# 467444_130_3_4-R0.net
KiCad netlist of a schematic drawn in Altium Designer
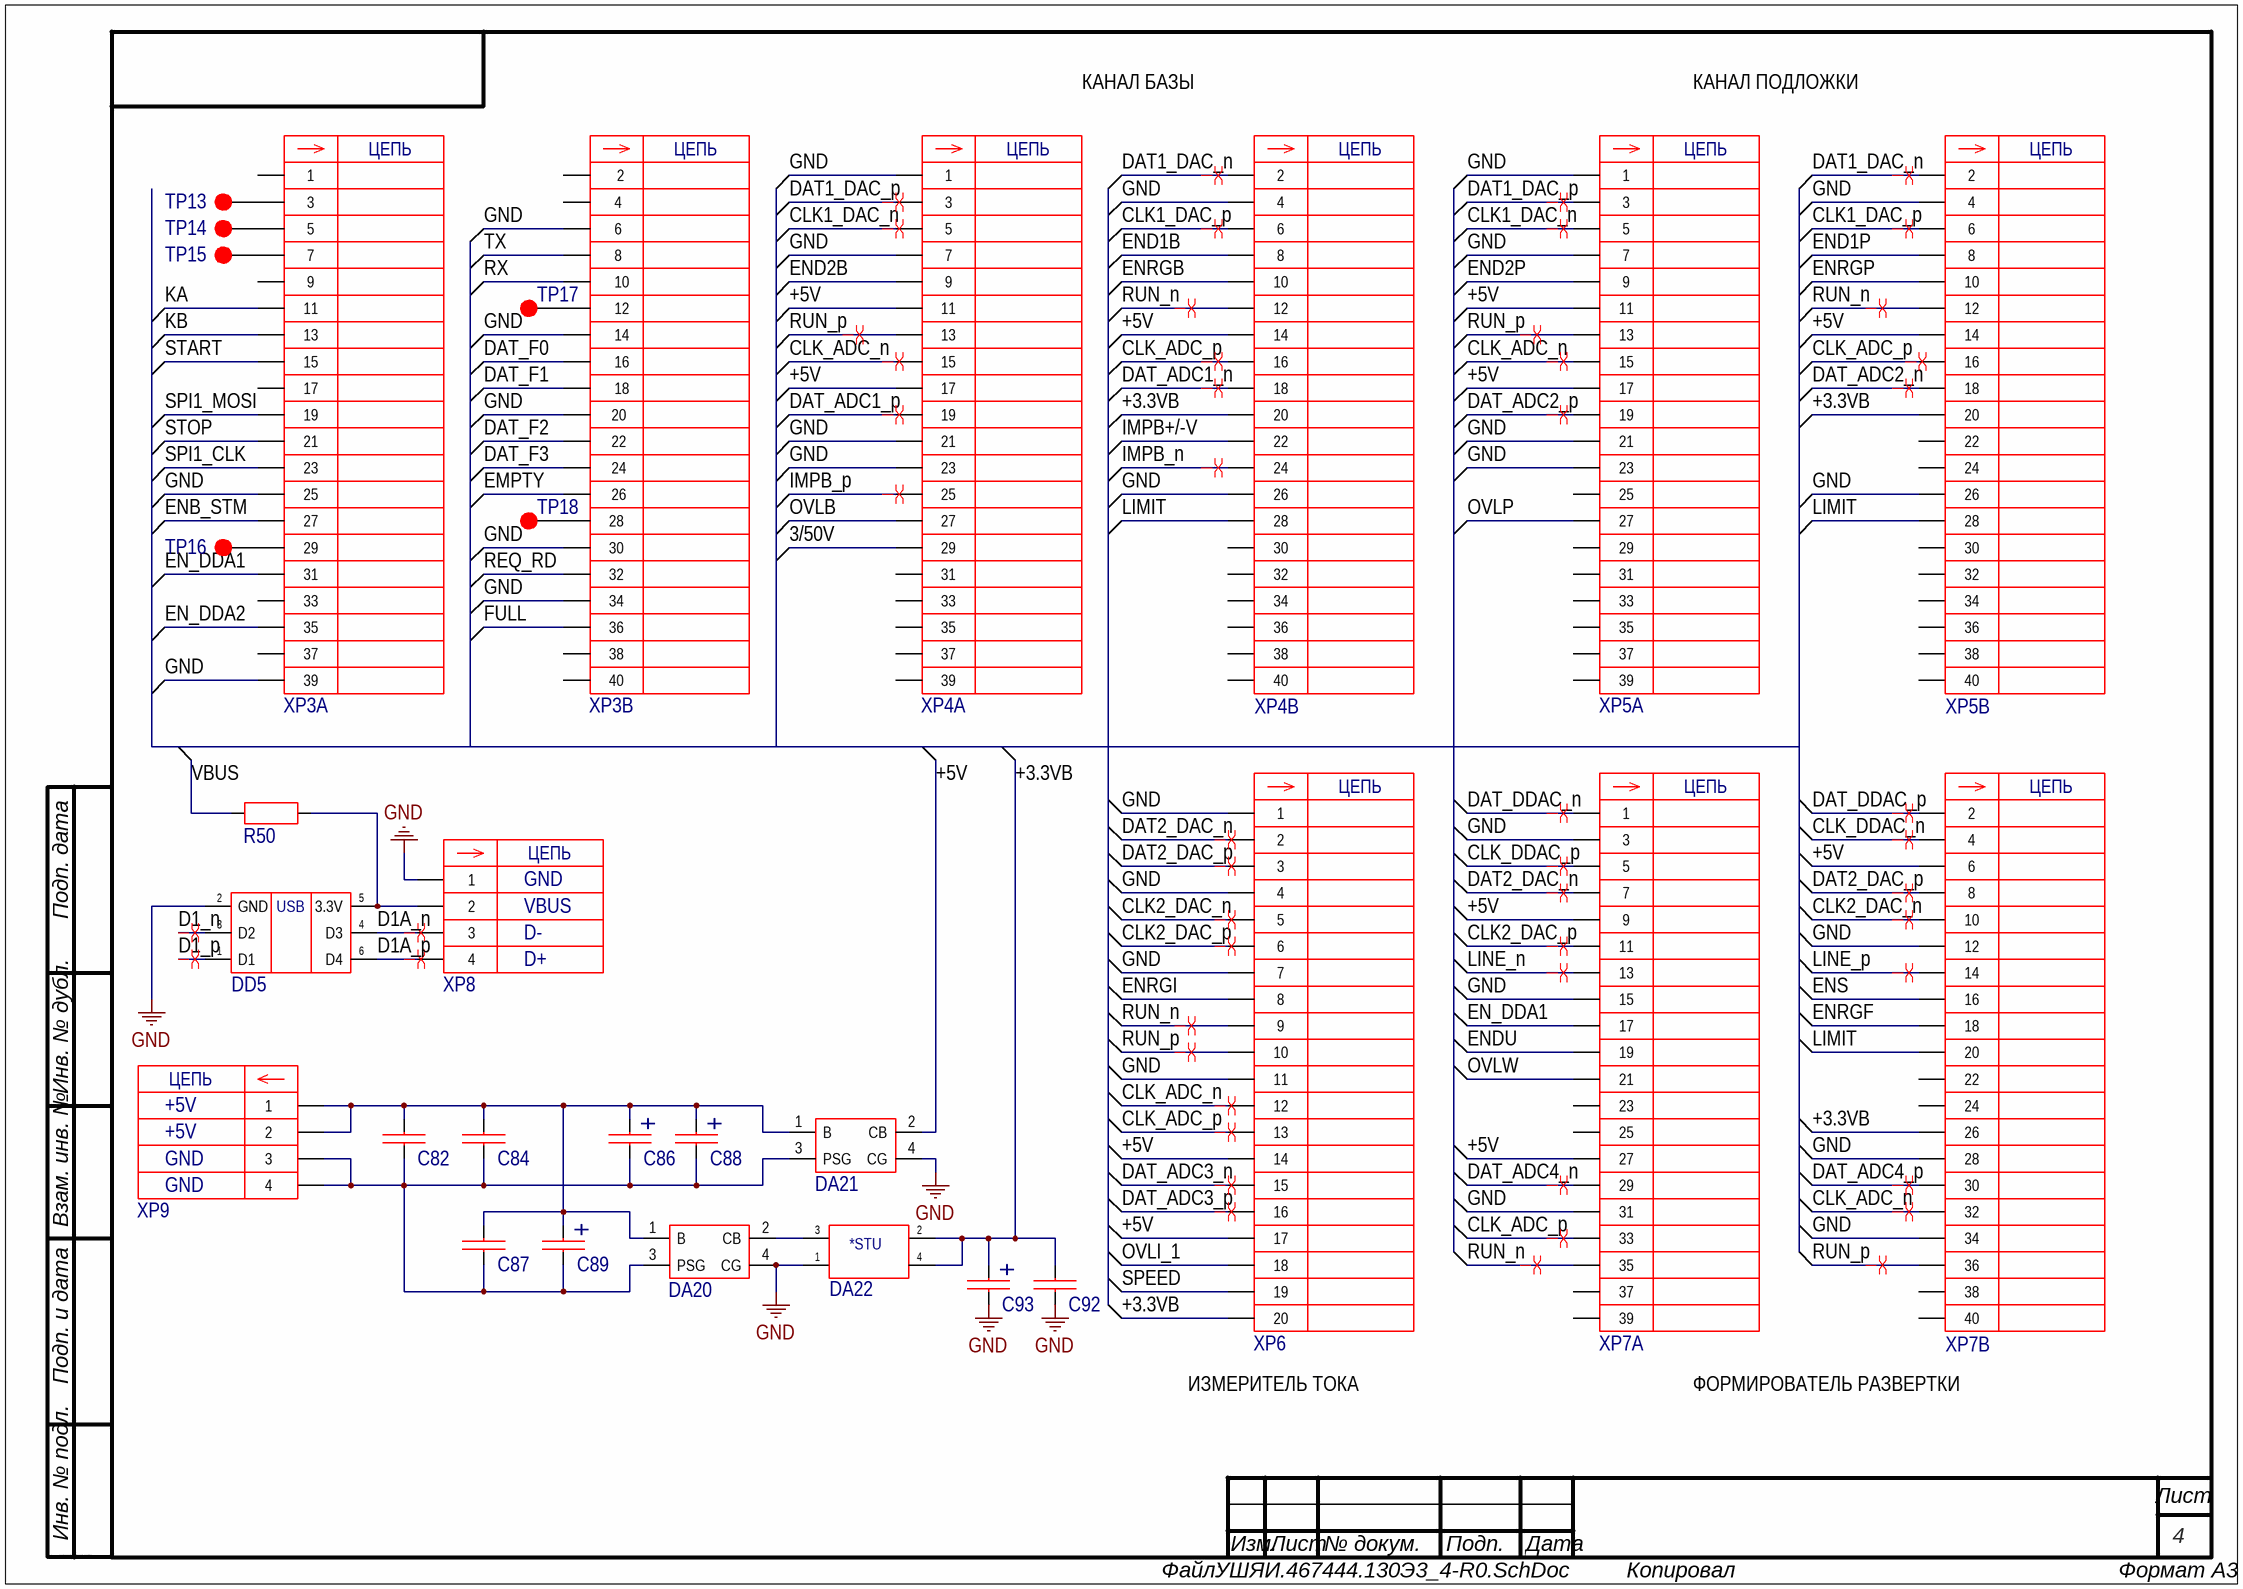
[diagram p0: УШЯИ.467444.130Э3_4-R0.SchDoc]

(export (version "E")
  (design (tool "Eeschema 10.0.6"))
  (components
    (comp (ref "C82")
      (value "0,1 µF")
      (footprint "C_0805 [2012 Metric]")
      (description "Неполярный конденсатор")
      (fields (field (name "MANUFACTURER") "Murata") (field (name "VOLTAGE") "50V"))
      (libsource (lib "lib") (part "C_const"))
    )
    (comp (ref "C84")
      (value "0,1 µF")
      (footprint "C_0805 [2012 Metric]")
      (description "Неполярный конденсатор")
      (fields (field (name "MANUFACTURER") "Murata") (field (name "VOLTAGE") "50V"))
      (libsource (lib "lib") (part "C_const"))
    )
    (comp (ref "C86")
      (value "1000 µF")
      (footprint "С_EXR_10x21")
      (description "Полярный конденсатор")
      (fields (field (name "MANUFACTURER") "Hitano") (field (name "VOLTAGE") "16V"))
      (libsource (lib "lib") (part "C_electrolytic"))
    )
    (comp (ref "C87")
      (value "0,1 µF")
      (footprint "C_0805 [2012 Metric]")
      (description "Неполярный конденсатор")
      (fields (field (name "MANUFACTURER") "Murata") (field (name "VOLTAGE") "50V"))
      (libsource (lib "lib") (part "C_const"))
    )
    (comp (ref "C88")
      (value "10 µF")
      (footprint "C+_1210 [3528-21 Metric]")
      (description "Полярный конденсатор")
      (fields (field (name "MANUFACTURER") "KYOCERA AVX") (field (name "VOLTAGE") "20V\r\n10V"))
      (libsource (lib "lib") (part "C_electrolytic"))
    )
    (comp (ref "C89")
      (value "10 µF")
      (footprint "C+_1210 [3528-21 Metric]")
      (description "Полярный конденсатор")
      (fields (field (name "MANUFACTURER") "KYOCERA AVX") (field (name "VOLTAGE") "20V\r\n10V"))
      (libsource (lib "lib") (part "C_electrolytic"))
    )
    (comp (ref "C92")
      (value "0,1 µF")
      (footprint "C_0805 [2012 Metric]")
      (description "Неполярный конденсатор")
      (fields (field (name "MANUFACTURER") "Murata") (field (name "VOLTAGE") "50V"))
      (libsource (lib "lib") (part "C_const"))
    )
    (comp (ref "C93")
      (value "10 µF")
      (footprint "C+_1210 [3528-21 Metric]")
      (description "Полярный конденсатор")
      (fields (field (name "MANUFACTURER") "KYOCERA AVX") (field (name "VOLTAGE") "20V\r\n10V"))
      (libsource (lib "lib") (part "C_electrolytic"))
    )
    (comp (ref "DA20")
      (value "BNX028-01")
      (footprint "F_BNX028-01")
      (description "16В, 35дБ")
      (fields (field (name "MANUFACTURER") "Murata Electronics"))
      (libsource (lib "lib") (part "F_BNX022-01"))
    )
    (comp (ref "DA21")
      (value "BNX028-01")
      (footprint "F_BNX028-01")
      (description "16В, 35дБ")
      (fields (field (name "MANUFACTURER") "Murata Electronics"))
      (libsource (lib "lib") (part "F_BNX022-01"))
    )
    (comp (ref "DA22")
      (value "LD1117AS33TR")
      (footprint "SOT-223")
      (description "IC, Fixed LDO Voltage Regulator, 5.3V to 10V, 1.15V Dropout, 3.3Vout, 1Aout")
      (fields (field (name "MANUFACTURER") "STMicroelectronics"))
      (libsource (lib "lib") (part "VolReg_LD1117AS33TR"))
    )
    (comp (ref "DD5")
      (value "USBUF01W6")
      (footprint "SOT-323-6")
      (description "EMI Filter, 2-Channel, USB Upstream Terminator, ESD Protection")
      (fields (field (name "MANUFACTURER") "STMicroelectronics"))
      (libsource (lib "lib") (part "USBUF01W6"))
    )
    (comp (ref "R50")
      (value "30R")
      (footprint "R_0805 [2012 Metric]")
      (fields (field (name "TOLERANCE") "±5%"))
      (libsource (lib "lib") (part "R_Const"))
    )
    (comp (ref "TP13") (value "~") (footprint "DSP_1.3") (libsource (lib "lib") (part "TP")))
    (comp (ref "TP14") (value "~") (footprint "DSP_1.3") (libsource (lib "lib") (part "TP")))
    (comp (ref "TP15") (value "~") (footprint "DSP_1.3") (libsource (lib "lib") (part "TP")))
    (comp (ref "TP16") (value "~") (footprint "DSP_1.3") (libsource (lib "lib") (part "TP")))
    (comp (ref "TP17") (value "~") (footprint "DSP_1.3") (libsource (lib "lib") (part "TP")))
    (comp (ref "TP18") (value "~") (footprint "DSP_1.3") (libsource (lib "lib") (part "TP")))
    (comp (ref "XP3")
      (value "BH-40")
      (footprint "BH-40")
      (description "Male, 40 pins, 2 rows, Vertical, DS1013-40S, 2.54 mm")
      (fields (field (name "MANUFACTURER") "Connfly electronic"))
      (libsource (lib "lib") (part "M_40"))
    )
    (comp (ref "XP4")
      (value "BH2-40")
      (footprint "BH2-40")
      (description "Male, 40 pins, 2 rows, Vertical, DS1014-40, 2 mm")
      (fields (field (name "MANUFACTURER") "Connfly electronic"))
      (libsource (lib "lib") (part "M_40"))
    )
    (comp (ref "XP5")
      (value "BH2-40")
      (footprint "BH2-40")
      (description "Male, 40 pins, 2 rows, Vertical, DS1014-40, 2 mm")
      (fields (field (name "MANUFACTURER") "Connfly electronic"))
      (libsource (lib "lib") (part "M_40"))
    )
    (comp (ref "XP6")
      (value "BH2-20R")
      (footprint "BH2-20R")
      (description "Male, 20 pins, 2 rows, Right Angle, DS1014-20RF1B-B, 2 mm")
      (fields (field (name "MANUFACTURER") "Connfly electronic"))
      (libsource (lib "lib") (part "M_20"))
    )
    (comp (ref "XP7")
      (value "BH2-40")
      (footprint "BH2-40")
      (description "Male, 40 pins, 2 rows, Vertical, DS1014-40, 2 mm")
      (fields (field (name "MANUFACTURER") "Connfly electronic"))
      (libsource (lib "lib") (part "M_40"))
    )
    (comp (ref "XP8")
      (value "AMPMODU II 280371-2")
      (footprint "AMP II-280371-2")
      (description "Male, 4 pin, 1 row, Vertical, Board-to-Board, 2.54 mm")
      (fields (field (name "MANUFACTURER") "TE Connectivity"))
      (libsource (lib "") (part "M_4_1"))
    )
    (comp (ref "XP9")
      (value "AMPMODU II 280371-2")
      (footprint "AMP II-280371-2")
      (description "Male, 4 pin, 1 row, Vertical, Board-to-Board, 2.54 mm")
      (fields (field (name "MANUFACTURER") "TE Connectivity"))
      (libsource (lib "lib") (part "M_4"))
    )
  )
  (nets
    (net (code "1") (name "/+3.3VB") (class "Default")
      (node (ref "C92") (pin "2") (pinfunction "2_2") (pintype "passive"))
      (node (ref "C93") (pin "+") (pinfunction "+_+") (pintype "passive"))
      (node (ref "DA22") (pin "2") (pinfunction "VOUT_2") (pintype "passive"))
      (node (ref "DA22") (pin "4") (pinfunction "VOUT_4") (pintype "passive"))
      (node (ref "XP4") (pin "20") (pinfunction "20_20") (pintype "passive"))
      (node (ref "XP5") (pin "20") (pinfunction "20_20") (pintype "passive"))
      (node (ref "XP6") (pin "20") (pinfunction "20_20") (pintype "passive"))
      (node (ref "XP7") (pin "26") (pinfunction "26_26") (pintype "passive"))
    )
    (net (code "2") (name "/+5V") (class "Default")
      (node (ref "DA21") (pin "2") (pinfunction "CB_2") (pintype "passive"))
      (node (ref "XP4") (pin "11") (pinfunction "11_11") (pintype "passive"))
      (node (ref "XP4") (pin "14") (pinfunction "14_14") (pintype "passive"))
      (node (ref "XP4") (pin "17") (pinfunction "17_17") (pintype "passive"))
      (node (ref "XP5") (pin "11") (pinfunction "11_11") (pintype "passive"))
      (node (ref "XP5") (pin "14") (pinfunction "14_14") (pintype "passive"))
      (node (ref "XP5") (pin "17") (pinfunction "17_17") (pintype "passive"))
      (node (ref "XP6") (pin "14") (pinfunction "14_14") (pintype "passive"))
      (node (ref "XP6") (pin "17") (pinfunction "17_17") (pintype "passive"))
      (node (ref "XP7") (pin "27") (pinfunction "27_27") (pintype "passive"))
      (node (ref "XP7") (pin "6") (pinfunction "6_6") (pintype "passive"))
      (node (ref "XP7") (pin "9") (pinfunction "9_9") (pintype "passive"))
    )
    (net (code "3") (name "/3{slash}50V") (class "Default")
      (node (ref "XP4") (pin "29") (pinfunction "29_29") (pintype "passive"))
    )
    (net (code "4") (name "/CLK1_DAC_n") (class "Default")
      (node (ref "XP4") (pin "5") (pinfunction "5_5") (pintype "passive"))
      (node (ref "XP5") (pin "5") (pinfunction "5_5") (pintype "passive"))
    )
    (net (code "5") (name "/CLK1_DAC_p") (class "Default")
      (node (ref "XP4") (pin "6") (pinfunction "6_6") (pintype "passive"))
      (node (ref "XP5") (pin "6") (pinfunction "6_6") (pintype "passive"))
    )
    (net (code "6") (name "/CLK2_DAC_n") (class "Default")
      (node (ref "XP6") (pin "5") (pinfunction "5_5") (pintype "passive"))
      (node (ref "XP7") (pin "10") (pinfunction "10_10") (pintype "passive"))
    )
    (net (code "7") (name "/CLK2_DAC_p") (class "Default")
      (node (ref "XP6") (pin "6") (pinfunction "6_6") (pintype "passive"))
      (node (ref "XP7") (pin "11") (pinfunction "11_11") (pintype "passive"))
    )
    (net (code "8") (name "/CLK_ADC_n") (class "Default")
      (node (ref "XP4") (pin "15") (pinfunction "15_15") (pintype "passive"))
      (node (ref "XP5") (pin "15") (pinfunction "15_15") (pintype "passive"))
      (node (ref "XP6") (pin "12") (pinfunction "12_12") (pintype "passive"))
      (node (ref "XP7") (pin "32") (pinfunction "32_32") (pintype "passive"))
    )
    (net (code "9") (name "/CLK_ADC_p") (class "Default")
      (node (ref "XP4") (pin "16") (pinfunction "16_16") (pintype "passive"))
      (node (ref "XP5") (pin "16") (pinfunction "16_16") (pintype "passive"))
      (node (ref "XP6") (pin "13") (pinfunction "13_13") (pintype "passive"))
      (node (ref "XP7") (pin "33") (pinfunction "33_33") (pintype "passive"))
    )
    (net (code "10") (name "/CLK_DDAC_n") (class "Default")
      (node (ref "XP7") (pin "4") (pinfunction "4_4") (pintype "passive"))
    )
    (net (code "11") (name "/CLK_DDAC_p") (class "Default")
      (node (ref "XP7") (pin "5") (pinfunction "5_5") (pintype "passive"))
    )
    (net (code "12") (name "/D1A_n") (class "Default")
      (node (ref "DD5") (pin "4") (pinfunction "D3_4") (pintype "passive"))
      (node (ref "XP8") (pin "3") (pinfunction "3_3") (pintype "passive"))
    )
    (net (code "13") (name "/D1A_p") (class "Default")
      (node (ref "DD5") (pin "6") (pinfunction "D4_6") (pintype "passive"))
      (node (ref "XP8") (pin "4") (pinfunction "4_4") (pintype "passive"))
    )
    (net (code "14") (name "/D1_n") (class "Default")
      (node (ref "DD5") (pin "3") (pinfunction "D2_3") (pintype "passive"))
    )
    (net (code "15") (name "/D1_p") (class "Default")
      (node (ref "DD5") (pin "1") (pinfunction "D1_1") (pintype "passive"))
    )
    (net (code "16") (name "/DAT1_DAC_n") (class "Default")
      (node (ref "XP4") (pin "2") (pinfunction "2_2") (pintype "passive"))
      (node (ref "XP5") (pin "2") (pinfunction "2_2") (pintype "passive"))
    )
    (net (code "17") (name "/DAT1_DAC_p") (class "Default")
      (node (ref "XP4") (pin "3") (pinfunction "3_3") (pintype "passive"))
      (node (ref "XP5") (pin "3") (pinfunction "3_3") (pintype "passive"))
    )
    (net (code "18") (name "/DAT2_DAC_n") (class "Default")
      (node (ref "XP6") (pin "2") (pinfunction "2_2") (pintype "passive"))
      (node (ref "XP7") (pin "7") (pinfunction "7_7") (pintype "passive"))
    )
    (net (code "19") (name "/DAT2_DAC_p") (class "Default")
      (node (ref "XP6") (pin "3") (pinfunction "3_3") (pintype "passive"))
      (node (ref "XP7") (pin "8") (pinfunction "8_8") (pintype "passive"))
    )
    (net (code "20") (name "/DAT_ADC1_n") (class "Default")
      (node (ref "XP4") (pin "18") (pinfunction "18_18") (pintype "passive"))
    )
    (net (code "21") (name "/DAT_ADC1_p") (class "Default")
      (node (ref "XP4") (pin "19") (pinfunction "19_19") (pintype "passive"))
    )
    (net (code "22") (name "/DAT_ADC2_n") (class "Default")
      (node (ref "XP5") (pin "18") (pinfunction "18_18") (pintype "passive"))
    )
    (net (code "23") (name "/DAT_ADC2_p") (class "Default")
      (node (ref "XP5") (pin "19") (pinfunction "19_19") (pintype "passive"))
    )
    (net (code "24") (name "/DAT_ADC3_n") (class "Default")
      (node (ref "XP6") (pin "15") (pinfunction "15_15") (pintype "passive"))
    )
    (net (code "25") (name "/DAT_ADC3_p") (class "Default")
      (node (ref "XP6") (pin "16") (pinfunction "16_16") (pintype "passive"))
    )
    (net (code "26") (name "/DAT_ADC4_n") (class "Default")
      (node (ref "XP7") (pin "29") (pinfunction "29_29") (pintype "passive"))
    )
    (net (code "27") (name "/DAT_ADC4_p") (class "Default")
      (node (ref "XP7") (pin "30") (pinfunction "30_30") (pintype "passive"))
    )
    (net (code "28") (name "/DAT_DDAC_n") (class "Default")
      (node (ref "XP7") (pin "1") (pinfunction "1_1") (pintype "passive"))
    )
    (net (code "29") (name "/DAT_DDAC_p") (class "Default")
      (node (ref "XP7") (pin "2") (pinfunction "2_2") (pintype "passive"))
    )
    (net (code "30") (name "/DAT_F0") (class "Default")
      (node (ref "XP3") (pin "16") (pinfunction "16_16") (pintype "passive"))
    )
    (net (code "31") (name "/DAT_F1") (class "Default")
      (node (ref "XP3") (pin "18") (pinfunction "18_18") (pintype "passive"))
    )
    (net (code "32") (name "/DAT_F2") (class "Default")
      (node (ref "XP3") (pin "22") (pinfunction "22_22") (pintype "passive"))
    )
    (net (code "33") (name "/DAT_F3") (class "Default")
      (node (ref "XP3") (pin "24") (pinfunction "24_24") (pintype "passive"))
    )
    (net (code "34") (name "/EMPTY") (class "Default")
      (node (ref "XP3") (pin "26") (pinfunction "26_26") (pintype "passive"))
    )
    (net (code "35") (name "/ENB_STM") (class "Default")
      (node (ref "XP3") (pin "27") (pinfunction "27_27") (pintype "passive"))
    )
    (net (code "36") (name "/END1B") (class "Default")
      (node (ref "XP4") (pin "8") (pinfunction "8_8") (pintype "passive"))
    )
    (net (code "37") (name "/END1P") (class "Default")
      (node (ref "XP5") (pin "8") (pinfunction "8_8") (pintype "passive"))
    )
    (net (code "38") (name "/END2B") (class "Default")
      (node (ref "XP4") (pin "9") (pinfunction "9_9") (pintype "passive"))
    )
    (net (code "39") (name "/END2P") (class "Default")
      (node (ref "XP5") (pin "9") (pinfunction "9_9") (pintype "passive"))
    )
    (net (code "40") (name "/ENDU") (class "Default")
      (node (ref "XP7") (pin "19") (pinfunction "19_19") (pintype "passive"))
    )
    (net (code "41") (name "/ENRGB") (class "Default")
      (node (ref "XP4") (pin "10") (pinfunction "10_10") (pintype "passive"))
    )
    (net (code "42") (name "/ENRGF") (class "Default")
      (node (ref "XP7") (pin "18") (pinfunction "18_18") (pintype "passive"))
    )
    (net (code "43") (name "/ENRGI") (class "Default")
      (node (ref "XP6") (pin "8") (pinfunction "8_8") (pintype "passive"))
    )
    (net (code "44") (name "/ENRGP") (class "Default")
      (node (ref "XP5") (pin "10") (pinfunction "10_10") (pintype "passive"))
    )
    (net (code "45") (name "/ENS") (class "Default")
      (node (ref "XP7") (pin "16") (pinfunction "16_16") (pintype "passive"))
    )
    (net (code "46") (name "/EN_DDA1") (class "Default")
      (node (ref "XP3") (pin "31") (pinfunction "31_31") (pintype "passive"))
      (node (ref "XP7") (pin "17") (pinfunction "17_17") (pintype "passive"))
    )
    (net (code "47") (name "/EN_DDA2") (class "Default")
      (node (ref "XP3") (pin "35") (pinfunction "35_35") (pintype "passive"))
    )
    (net (code "48") (name "/FULL") (class "Default")
      (node (ref "XP3") (pin "36") (pinfunction "36_36") (pintype "passive"))
    )
    (net (code "49") (name "/IMPB+{slash}-V") (class "Default")
      (node (ref "XP4") (pin "22") (pinfunction "22_22") (pintype "passive"))
    )
    (net (code "50") (name "/IMPB_n") (class "Default")
      (node (ref "XP4") (pin "24") (pinfunction "24_24") (pintype "passive"))
    )
    (net (code "51") (name "/IMPB_p") (class "Default")
      (node (ref "XP4") (pin "25") (pinfunction "25_25") (pintype "passive"))
    )
    (net (code "52") (name "/KA") (class "Default")
      (node (ref "XP3") (pin "11") (pinfunction "11_11") (pintype "passive"))
    )
    (net (code "53") (name "/KB") (class "Default")
      (node (ref "XP3") (pin "13") (pinfunction "13_13") (pintype "passive"))
    )
    (net (code "54") (name "/LIMIT") (class "Default")
      (node (ref "XP4") (pin "28") (pinfunction "28_28") (pintype "passive"))
      (node (ref "XP5") (pin "28") (pinfunction "28_28") (pintype "passive"))
      (node (ref "XP7") (pin "20") (pinfunction "20_20") (pintype "passive"))
    )
    (net (code "55") (name "/LINE_n") (class "Default")
      (node (ref "XP7") (pin "13") (pinfunction "13_13") (pintype "passive"))
    )
    (net (code "56") (name "/LINE_p") (class "Default")
      (node (ref "XP7") (pin "14") (pinfunction "14_14") (pintype "passive"))
    )
    (net (code "57") (name "/OVLB") (class "Default")
      (node (ref "XP4") (pin "27") (pinfunction "27_27") (pintype "passive"))
    )
    (net (code "58") (name "/OVLI_1") (class "Default")
      (node (ref "XP6") (pin "18") (pinfunction "18_18") (pintype "passive"))
    )
    (net (code "59") (name "/OVLP") (class "Default")
      (node (ref "XP5") (pin "27") (pinfunction "27_27") (pintype "passive"))
    )
    (net (code "60") (name "/OVLW") (class "Default")
      (node (ref "XP7") (pin "21") (pinfunction "21_21") (pintype "passive"))
    )
    (net (code "61") (name "/REQ_RD") (class "Default")
      (node (ref "XP3") (pin "32") (pinfunction "32_32") (pintype "passive"))
    )
    (net (code "62") (name "/RUN_n") (class "Default")
      (node (ref "XP4") (pin "12") (pinfunction "12_12") (pintype "passive"))
      (node (ref "XP5") (pin "12") (pinfunction "12_12") (pintype "passive"))
      (node (ref "XP6") (pin "9") (pinfunction "9_9") (pintype "passive"))
      (node (ref "XP7") (pin "35") (pinfunction "35_35") (pintype "passive"))
    )
    (net (code "63") (name "/RUN_p") (class "Default")
      (node (ref "XP4") (pin "13") (pinfunction "13_13") (pintype "passive"))
      (node (ref "XP5") (pin "13") (pinfunction "13_13") (pintype "passive"))
      (node (ref "XP6") (pin "10") (pinfunction "10_10") (pintype "passive"))
      (node (ref "XP7") (pin "36") (pinfunction "36_36") (pintype "passive"))
    )
    (net (code "64") (name "/RX") (class "Default")
      (node (ref "XP3") (pin "10") (pinfunction "10_10") (pintype "passive"))
    )
    (net (code "65") (name "/SPEED") (class "Default")
      (node (ref "XP6") (pin "19") (pinfunction "19_19") (pintype "passive"))
    )
    (net (code "66") (name "/SPI1_CLK") (class "Default")
      (node (ref "XP3") (pin "23") (pinfunction "23_23") (pintype "passive"))
    )
    (net (code "67") (name "/SPI1_MOSI") (class "Default")
      (node (ref "XP3") (pin "19") (pinfunction "19_19") (pintype "passive"))
    )
    (net (code "68") (name "/START") (class "Default")
      (node (ref "XP3") (pin "15") (pinfunction "15_15") (pintype "passive"))
    )
    (net (code "69") (name "/STOP") (class "Default")
      (node (ref "XP3") (pin "21") (pinfunction "21_21") (pintype "passive"))
    )
    (net (code "70") (name "/TX") (class "Default")
      (node (ref "XP3") (pin "8") (pinfunction "8_8") (pintype "passive"))
    )
    (net (code "71") (name "/VBUS") (class "Default")
      (node (ref "R50") (pin "1") (pinfunction "1_1") (pintype "passive"))
    )
    (net (code "72") (name "GND") (class "Default")
      (node (ref "C92") (pin "1") (pinfunction "1_1") (pintype "passive"))
      (node (ref "C93") (pin "-") (pinfunction "-_-") (pintype "passive"))
      (node (ref "DA20") (pin "4") (pinfunction "CG_4") (pintype "passive"))
      (node (ref "DA21") (pin "4") (pinfunction "CG_4") (pintype "passive"))
      (node (ref "DA22") (pin "1") (pinfunction "ADJ/GND_1") (pintype "passive"))
      (node (ref "DD5") (pin "2") (pinfunction "GND_2") (pintype "passive"))
      (node (ref "XP3") (pin "14") (pinfunction "14_14") (pintype "passive"))
      (node (ref "XP3") (pin "20") (pinfunction "20_20") (pintype "passive"))
      (node (ref "XP3") (pin "25") (pinfunction "25_25") (pintype "passive"))
      (node (ref "XP3") (pin "30") (pinfunction "30_30") (pintype "passive"))
      (node (ref "XP3") (pin "34") (pinfunction "34_34") (pintype "passive"))
      (node (ref "XP3") (pin "39") (pinfunction "39_39") (pintype "passive"))
      (node (ref "XP3") (pin "6") (pinfunction "6_6") (pintype "passive"))
      (node (ref "XP4") (pin "1") (pinfunction "1_1") (pintype "passive"))
      (node (ref "XP4") (pin "21") (pinfunction "21_21") (pintype "passive"))
      (node (ref "XP4") (pin "23") (pinfunction "23_23") (pintype "passive"))
      (node (ref "XP4") (pin "26") (pinfunction "26_26") (pintype "passive"))
      (node (ref "XP4") (pin "4") (pinfunction "4_4") (pintype "passive"))
      (node (ref "XP4") (pin "7") (pinfunction "7_7") (pintype "passive"))
      (node (ref "XP5") (pin "1") (pinfunction "1_1") (pintype "passive"))
      (node (ref "XP5") (pin "21") (pinfunction "21_21") (pintype "passive"))
      (node (ref "XP5") (pin "23") (pinfunction "23_23") (pintype "passive"))
      (node (ref "XP5") (pin "26") (pinfunction "26_26") (pintype "passive"))
      (node (ref "XP5") (pin "4") (pinfunction "4_4") (pintype "passive"))
      (node (ref "XP5") (pin "7") (pinfunction "7_7") (pintype "passive"))
      (node (ref "XP6") (pin "1") (pinfunction "1_1") (pintype "passive"))
      (node (ref "XP6") (pin "11") (pinfunction "11_11") (pintype "passive"))
      (node (ref "XP6") (pin "4") (pinfunction "4_4") (pintype "passive"))
      (node (ref "XP6") (pin "7") (pinfunction "7_7") (pintype "passive"))
      (node (ref "XP7") (pin "12") (pinfunction "12_12") (pintype "passive"))
      (node (ref "XP7") (pin "15") (pinfunction "15_15") (pintype "passive"))
      (node (ref "XP7") (pin "28") (pinfunction "28_28") (pintype "passive"))
      (node (ref "XP7") (pin "3") (pinfunction "3_3") (pintype "passive"))
      (node (ref "XP7") (pin "31") (pinfunction "31_31") (pintype "passive"))
      (node (ref "XP7") (pin "34") (pinfunction "34_34") (pintype "passive"))
      (node (ref "XP8") (pin "1") (pinfunction "1_1") (pintype "passive"))
    )
    (net (code "73") (name "Net-(DA20-B)") (class "Default")
      (node (ref "C82") (pin "1") (pinfunction "1_1") (pintype "passive"))
      (node (ref "C84") (pin "1") (pinfunction "1_1") (pintype "passive"))
      (node (ref "C86") (pin "+") (pinfunction "+_+") (pintype "passive"))
      (node (ref "C87") (pin "2") (pinfunction "2_2") (pintype "passive"))
      (node (ref "C88") (pin "+") (pinfunction "+_+") (pintype "passive"))
      (node (ref "C89") (pin "+") (pinfunction "+_+") (pintype "passive"))
      (node (ref "DA20") (pin "1") (pinfunction "B_1") (pintype "passive"))
      (node (ref "DA21") (pin "1") (pinfunction "B_1") (pintype "passive"))
      (node (ref "XP9") (pin "1") (pinfunction "1_1") (pintype "passive"))
      (node (ref "XP9") (pin "2") (pinfunction "2_2") (pintype "passive"))
    )
    (net (code "74") (name "Net-(DA20-CB)") (class "Default")
      (node (ref "DA20") (pin "2") (pinfunction "CB_2") (pintype "passive"))
      (node (ref "DA22") (pin "3") (pinfunction "VIN_3") (pintype "passive"))
    )
    (net (code "75") (name "Net-(DA20-PSG)") (class "Default")
      (node (ref "C82") (pin "2") (pinfunction "2_2") (pintype "passive"))
      (node (ref "C84") (pin "2") (pinfunction "2_2") (pintype "passive"))
      (node (ref "C86") (pin "-") (pinfunction "-_-") (pintype "passive"))
      (node (ref "C87") (pin "1") (pinfunction "1_1") (pintype "passive"))
      (node (ref "C88") (pin "-") (pinfunction "-_-") (pintype "passive"))
      (node (ref "C89") (pin "-") (pinfunction "-_-") (pintype "passive"))
      (node (ref "DA20") (pin "3") (pinfunction "PSG_3") (pintype "passive"))
      (node (ref "DA21") (pin "3") (pinfunction "PSG_3") (pintype "passive"))
      (node (ref "XP9") (pin "3") (pinfunction "3_3") (pintype "passive"))
      (node (ref "XP9") (pin "4") (pinfunction "4_4") (pintype "passive"))
    )
    (net (code "76") (name "Net-(DD5-3.3V)") (class "Default")
      (node (ref "DD5") (pin "5") (pinfunction "3.3V_5") (pintype "passive"))
      (node (ref "R50") (pin "2") (pinfunction "2_2") (pintype "passive"))
      (node (ref "XP8") (pin "2") (pinfunction "2_2") (pintype "passive"))
    )
    (net (code "77") (name "Net-(TP13-Pad1)") (class "Default")
      (node (ref "TP13") (pin "1") (pinfunction "1_1") (pintype "passive"))
      (node (ref "XP3") (pin "3") (pinfunction "3_3") (pintype "passive"))
    )
    (net (code "78") (name "Net-(TP14-Pad1)") (class "Default")
      (node (ref "TP14") (pin "1") (pinfunction "1_1") (pintype "passive"))
      (node (ref "XP3") (pin "5") (pinfunction "5_5") (pintype "passive"))
    )
    (net (code "79") (name "Net-(TP15-Pad1)") (class "Default")
      (node (ref "TP15") (pin "1") (pinfunction "1_1") (pintype "passive"))
      (node (ref "XP3") (pin "7") (pinfunction "7_7") (pintype "passive"))
    )
    (net (code "80") (name "Net-(TP16-Pad1)") (class "Default")
      (node (ref "TP16") (pin "1") (pinfunction "1_1") (pintype "passive"))
      (node (ref "XP3") (pin "29") (pinfunction "29_29") (pintype "passive"))
    )
    (net (code "81") (name "Net-(TP17-Pad1)") (class "Default")
      (node (ref "TP17") (pin "1") (pinfunction "1_1") (pintype "passive"))
      (node (ref "XP3") (pin "12") (pinfunction "12_12") (pintype "passive"))
    )
    (net (code "82") (name "Net-(TP18-Pad1)") (class "Default")
      (node (ref "TP18") (pin "1") (pinfunction "1_1") (pintype "passive"))
      (node (ref "XP3") (pin "28") (pinfunction "28_28") (pintype "passive"))
    )
    (net (code "83") (name "unconnected-(XP3-Pad1)") (class "Default")
      (node (ref "XP3") (pin "1") (pinfunction "1_1") (pintype "passive"))
    )
    (net (code "84") (name "unconnected-(XP3-Pad2)") (class "Default")
      (node (ref "XP3") (pin "2") (pinfunction "2_2") (pintype "passive"))
    )
    (net (code "85") (name "unconnected-(XP3-Pad4)") (class "Default")
      (node (ref "XP3") (pin "4") (pinfunction "4_4") (pintype "passive"))
    )
    (net (code "86") (name "unconnected-(XP3-Pad9)") (class "Default")
      (node (ref "XP3") (pin "9") (pinfunction "9_9") (pintype "passive"))
    )
    (net (code "87") (name "unconnected-(XP3-Pad17)") (class "Default")
      (node (ref "XP3") (pin "17") (pinfunction "17_17") (pintype "passive"))
    )
    (net (code "88") (name "unconnected-(XP3-Pad33)") (class "Default")
      (node (ref "XP3") (pin "33") (pinfunction "33_33") (pintype "passive"))
    )
    (net (code "89") (name "unconnected-(XP3-Pad37)") (class "Default")
      (node (ref "XP3") (pin "37") (pinfunction "37_37") (pintype "passive"))
    )
    (net (code "90") (name "unconnected-(XP3-Pad38)") (class "Default")
      (node (ref "XP3") (pin "38") (pinfunction "38_38") (pintype "passive"))
    )
    (net (code "91") (name "unconnected-(XP3-Pad40)") (class "Default")
      (node (ref "XP3") (pin "40") (pinfunction "40_40") (pintype "passive"))
    )
    (net (code "92") (name "unconnected-(XP4-Pad30)") (class "Default")
      (node (ref "XP4") (pin "30") (pinfunction "30_30") (pintype "passive"))
    )
    (net (code "93") (name "unconnected-(XP4-Pad31)") (class "Default")
      (node (ref "XP4") (pin "31") (pinfunction "31_31") (pintype "passive"))
    )
    (net (code "94") (name "unconnected-(XP4-Pad32)") (class "Default")
      (node (ref "XP4") (pin "32") (pinfunction "32_32") (pintype "passive"))
    )
    (net (code "95") (name "unconnected-(XP4-Pad33)") (class "Default")
      (node (ref "XP4") (pin "33") (pinfunction "33_33") (pintype "passive"))
    )
    (net (code "96") (name "unconnected-(XP4-Pad34)") (class "Default")
      (node (ref "XP4") (pin "34") (pinfunction "34_34") (pintype "passive"))
    )
    (net (code "97") (name "unconnected-(XP4-Pad35)") (class "Default")
      (node (ref "XP4") (pin "35") (pinfunction "35_35") (pintype "passive"))
    )
    (net (code "98") (name "unconnected-(XP4-Pad36)") (class "Default")
      (node (ref "XP4") (pin "36") (pinfunction "36_36") (pintype "passive"))
    )
    (net (code "99") (name "unconnected-(XP4-Pad37)") (class "Default")
      (node (ref "XP4") (pin "37") (pinfunction "37_37") (pintype "passive"))
    )
    (net (code "100") (name "unconnected-(XP4-Pad38)") (class "Default")
      (node (ref "XP4") (pin "38") (pinfunction "38_38") (pintype "passive"))
    )
    (net (code "101") (name "unconnected-(XP4-Pad39)") (class "Default")
      (node (ref "XP4") (pin "39") (pinfunction "39_39") (pintype "passive"))
    )
    (net (code "102") (name "unconnected-(XP4-Pad40)") (class "Default")
      (node (ref "XP4") (pin "40") (pinfunction "40_40") (pintype "passive"))
    )
    (net (code "103") (name "unconnected-(XP5-Pad22)") (class "Default")
      (node (ref "XP5") (pin "22") (pinfunction "22_22") (pintype "passive"))
    )
    (net (code "104") (name "unconnected-(XP5-Pad24)") (class "Default")
      (node (ref "XP5") (pin "24") (pinfunction "24_24") (pintype "passive"))
    )
    (net (code "105") (name "unconnected-(XP5-Pad25)") (class "Default")
      (node (ref "XP5") (pin "25") (pinfunction "25_25") (pintype "passive"))
    )
    (net (code "106") (name "unconnected-(XP5-Pad29)") (class "Default")
      (node (ref "XP5") (pin "29") (pinfunction "29_29") (pintype "passive"))
    )
    (net (code "107") (name "unconnected-(XP5-Pad30)") (class "Default")
      (node (ref "XP5") (pin "30") (pinfunction "30_30") (pintype "passive"))
    )
    (net (code "108") (name "unconnected-(XP5-Pad31)") (class "Default")
      (node (ref "XP5") (pin "31") (pinfunction "31_31") (pintype "passive"))
    )
    (net (code "109") (name "unconnected-(XP5-Pad32)") (class "Default")
      (node (ref "XP5") (pin "32") (pinfunction "32_32") (pintype "passive"))
    )
    (net (code "110") (name "unconnected-(XP5-Pad33)") (class "Default")
      (node (ref "XP5") (pin "33") (pinfunction "33_33") (pintype "passive"))
    )
    (net (code "111") (name "unconnected-(XP5-Pad34)") (class "Default")
      (node (ref "XP5") (pin "34") (pinfunction "34_34") (pintype "passive"))
    )
    (net (code "112") (name "unconnected-(XP5-Pad35)") (class "Default")
      (node (ref "XP5") (pin "35") (pinfunction "35_35") (pintype "passive"))
    )
    (net (code "113") (name "unconnected-(XP5-Pad36)") (class "Default")
      (node (ref "XP5") (pin "36") (pinfunction "36_36") (pintype "passive"))
    )
    (net (code "114") (name "unconnected-(XP5-Pad37)") (class "Default")
      (node (ref "XP5") (pin "37") (pinfunction "37_37") (pintype "passive"))
    )
    (net (code "115") (name "unconnected-(XP5-Pad38)") (class "Default")
      (node (ref "XP5") (pin "38") (pinfunction "38_38") (pintype "passive"))
    )
    (net (code "116") (name "unconnected-(XP5-Pad39)") (class "Default")
      (node (ref "XP5") (pin "39") (pinfunction "39_39") (pintype "passive"))
    )
    (net (code "117") (name "unconnected-(XP5-Pad40)") (class "Default")
      (node (ref "XP5") (pin "40") (pinfunction "40_40") (pintype "passive"))
    )
    (net (code "118") (name "unconnected-(XP7-Pad22)") (class "Default")
      (node (ref "XP7") (pin "22") (pinfunction "22_22") (pintype "passive"))
    )
    (net (code "119") (name "unconnected-(XP7-Pad23)") (class "Default")
      (node (ref "XP7") (pin "23") (pinfunction "23_23") (pintype "passive"))
    )
    (net (code "120") (name "unconnected-(XP7-Pad24)") (class "Default")
      (node (ref "XP7") (pin "24") (pinfunction "24_24") (pintype "passive"))
    )
    (net (code "121") (name "unconnected-(XP7-Pad25)") (class "Default")
      (node (ref "XP7") (pin "25") (pinfunction "25_25") (pintype "passive"))
    )
    (net (code "122") (name "unconnected-(XP7-Pad37)") (class "Default")
      (node (ref "XP7") (pin "37") (pinfunction "37_37") (pintype "passive"))
    )
    (net (code "123") (name "unconnected-(XP7-Pad38)") (class "Default")
      (node (ref "XP7") (pin "38") (pinfunction "38_38") (pintype "passive"))
    )
    (net (code "124") (name "unconnected-(XP7-Pad39)") (class "Default")
      (node (ref "XP7") (pin "39") (pinfunction "39_39") (pintype "passive"))
    )
    (net (code "125") (name "unconnected-(XP7-Pad40)") (class "Default")
      (node (ref "XP7") (pin "40") (pinfunction "40_40") (pintype "passive"))
    )
  )
)
